# 20_FPGA_Power.net
KiCad netlist of a schematic drawn in Altium Designer
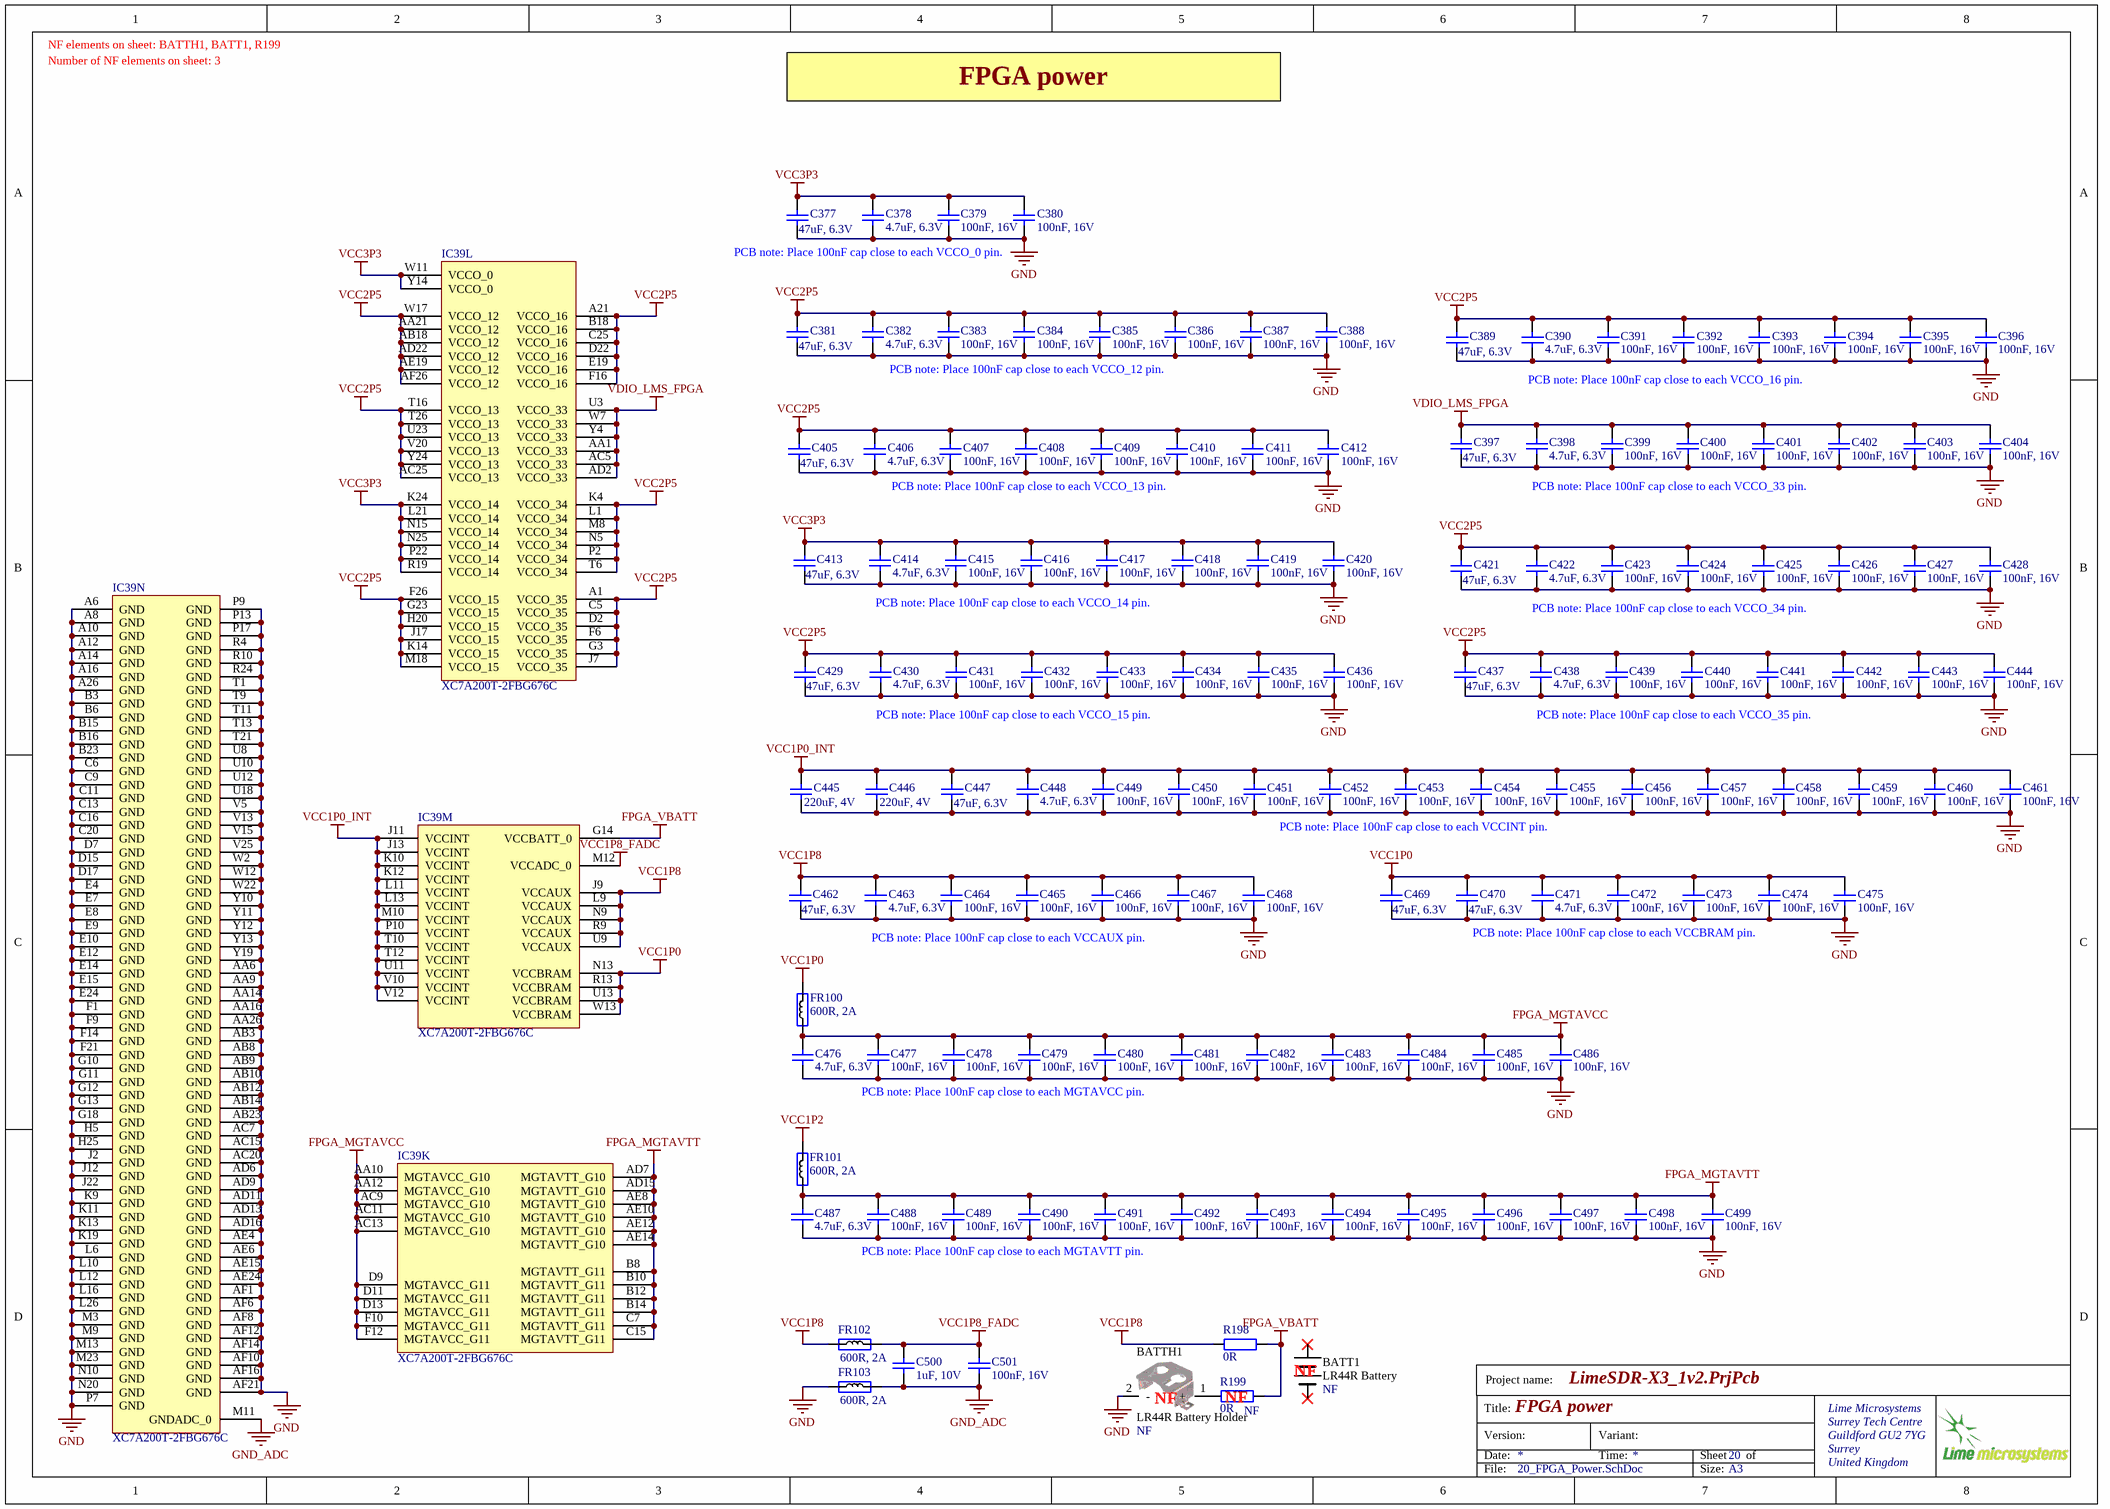
[diagram p0: 20_FPGA_Power.SchDoc]

(export (version "E")
  (design (tool "Eeschema 10.0.6"))
  (components
    (comp (ref "BATT1")
      (value "LR44R Battery")
      (fields (field (name "MANUFACTURER") "Murata") (field (name "ASSEMBLY INFO") "NF"))
      (libsource (lib "LimeMicroAltiumLib_schLib_r03") (part "LR44R_BATTERY"))
    )
    (comp (ref "BATTH1")
      (value "LR44R Battery Holder")
      (footprint "LR44R_BATTERY_HOLDER")
      (fields (field (name "MANUFACTURER") "Keystone Electronics") (field (name "ASSEMBLY INFO") "NF"))
      (libsource (lib "LimeMicroAltiumLib_schLib_r04") (part "LR44R_BATTERY_HOLDER"))
    )
    (comp (ref "C377")
      (value "47uF, 6.3V")
      (footprint "CAP1206")
      (fields
        (field (name "TOLERANCE") "±20%")
        (field (name "MANUFACTURER") "Samsung Electro-Mechanics")
        (field (name "MANUFACTURER PART NUMBER") "CL31A476MQHNNNE")
      )
      (libsource (lib "") (part "Cap_1206_2"))
    )
    (comp (ref "C378")
      (value "4.7uF, 6.3V")
      (footprint "CAP0402")
      (fields
        (field (name "MANUFACTURER") "Murata Electronics North America")
        (field (name "TOLERANCE") "±20%")
      )
      (libsource (lib "LimeMicroAltiumLib_schLib") (part "Cap_0402"))
    )
    (comp (ref "C379")
      (value "100nF, 16V")
      (footprint "CAP0402")
      (fields (field (name "MANUFACTURER") "Murata Electronics") (field (name "TOLERANCE") "10 %"))
      (libsource (lib "LimeMicroAltiumLib_schLib") (part "Cap_0402"))
    )
    (comp (ref "C380")
      (value "100nF, 16V")
      (footprint "CAP0402")
      (fields (field (name "MANUFACTURER") "Murata Electronics") (field (name "TOLERANCE") "10 %"))
      (libsource (lib "LimeMicroAltiumLib_schLib") (part "Cap_0402"))
    )
    (comp (ref "C381")
      (value "47uF, 6.3V")
      (footprint "CAP1206")
      (fields
        (field (name "TOLERANCE") "±20%")
        (field (name "MANUFACTURER") "Samsung Electro-Mechanics")
        (field (name "MANUFACTURER PART NUMBER") "CL31A476MQHNNNE")
      )
      (libsource (lib "") (part "Cap_1206_2"))
    )
    (comp (ref "C382")
      (value "4.7uF, 6.3V")
      (footprint "CAP0402")
      (fields
        (field (name "MANUFACTURER") "Murata Electronics North America")
        (field (name "TOLERANCE") "±20%")
      )
      (libsource (lib "LimeMicroAltiumLib_schLib") (part "Cap_0402"))
    )
    (comp (ref "C383")
      (value "100nF, 16V")
      (footprint "CAP0402")
      (fields (field (name "MANUFACTURER") "Murata Electronics") (field (name "TOLERANCE") "10 %"))
      (libsource (lib "LimeMicroAltiumLib_schLib") (part "Cap_0402"))
    )
    (comp (ref "C384")
      (value "100nF, 16V")
      (footprint "CAP0402")
      (fields (field (name "MANUFACTURER") "Murata Electronics") (field (name "TOLERANCE") "10 %"))
      (libsource (lib "LimeMicroAltiumLib_schLib") (part "Cap_0402"))
    )
    (comp (ref "C385")
      (value "100nF, 16V")
      (footprint "CAP0402")
      (fields (field (name "MANUFACTURER") "Murata Electronics") (field (name "TOLERANCE") "10 %"))
      (libsource (lib "") (part "Cap_0402_3"))
    )
    (comp (ref "C386")
      (value "100nF, 16V")
      (footprint "CAP0402")
      (fields (field (name "MANUFACTURER") "Murata Electronics") (field (name "TOLERANCE") "10 %"))
      (libsource (lib "") (part "Cap_0402_1"))
    )
    (comp (ref "C387")
      (value "100nF, 16V")
      (footprint "CAP0402")
      (fields (field (name "MANUFACTURER") "Murata Electronics") (field (name "TOLERANCE") "10 %"))
      (libsource (lib "") (part "Cap_0402_1"))
    )
    (comp (ref "C388")
      (value "100nF, 16V")
      (footprint "CAP0402")
      (fields (field (name "MANUFACTURER") "Murata Electronics") (field (name "TOLERANCE") "10 %"))
      (libsource (lib "LimeMicroAltiumLib_schLib") (part "Cap_0402"))
    )
    (comp (ref "C389")
      (value "47uF, 6.3V")
      (footprint "CAP1206")
      (fields
        (field (name "TOLERANCE") "±20%")
        (field (name "MANUFACTURER") "Samsung Electro-Mechanics")
        (field (name "MANUFACTURER PART NUMBER") "CL31A476MQHNNNE")
      )
      (libsource (lib "") (part "Cap_1206_2"))
    )
    (comp (ref "C390")
      (value "4.7uF, 6.3V")
      (footprint "CAP0402")
      (fields
        (field (name "MANUFACTURER") "Murata Electronics North America")
        (field (name "TOLERANCE") "±20%")
      )
      (libsource (lib "LimeMicroAltiumLib_schLib") (part "Cap_0402"))
    )
    (comp (ref "C391")
      (value "100nF, 16V")
      (footprint "CAP0402")
      (fields (field (name "MANUFACTURER") "Murata Electronics") (field (name "TOLERANCE") "10 %"))
      (libsource (lib "LimeMicroAltiumLib_schLib") (part "Cap_0402"))
    )
    (comp (ref "C392")
      (value "100nF, 16V")
      (footprint "CAP0402")
      (fields (field (name "MANUFACTURER") "Murata Electronics") (field (name "TOLERANCE") "10 %"))
      (libsource (lib "LimeMicroAltiumLib_schLib") (part "Cap_0402"))
    )
    (comp (ref "C393")
      (value "100nF, 16V")
      (footprint "CAP0402")
      (fields (field (name "MANUFACTURER") "Murata Electronics") (field (name "TOLERANCE") "10 %"))
      (libsource (lib "") (part "Cap_0402_3"))
    )
    (comp (ref "C394")
      (value "100nF, 16V")
      (footprint "CAP0402")
      (fields (field (name "MANUFACTURER") "Murata Electronics") (field (name "TOLERANCE") "10 %"))
      (libsource (lib "") (part "Cap_0402_1"))
    )
    (comp (ref "C395")
      (value "100nF, 16V")
      (footprint "CAP0402")
      (fields (field (name "MANUFACTURER") "Murata Electronics") (field (name "TOLERANCE") "10 %"))
      (libsource (lib "") (part "Cap_0402_1"))
    )
    (comp (ref "C396")
      (value "100nF, 16V")
      (footprint "CAP0402")
      (fields (field (name "MANUFACTURER") "Murata Electronics") (field (name "TOLERANCE") "10 %"))
      (libsource (lib "LimeMicroAltiumLib_schLib") (part "Cap_0402"))
    )
    (comp (ref "C397")
      (value "47uF, 6.3V")
      (footprint "CAP1206")
      (fields
        (field (name "TOLERANCE") "±20%")
        (field (name "MANUFACTURER") "Samsung Electro-Mechanics")
        (field (name "MANUFACTURER PART NUMBER") "CL31A476MQHNNNE")
      )
      (libsource (lib "LimeFPGAboard_schLib") (part "Cap_1206"))
    )
    (comp (ref "C398")
      (value "4.7uF, 6.3V")
      (footprint "CAP0402")
      (fields
        (field (name "MANUFACTURER") "Murata Electronics North America")
        (field (name "TOLERANCE") "±20%")
      )
      (libsource (lib "LimeMicroAltiumLib_schLib") (part "Cap_0402"))
    )
    (comp (ref "C399")
      (value "100nF, 16V")
      (footprint "CAP0402")
      (fields (field (name "MANUFACTURER") "Murata Electronics") (field (name "TOLERANCE") "10 %"))
      (libsource (lib "") (part "Cap_0402_1"))
    )
    (comp (ref "C400")
      (value "100nF, 16V")
      (footprint "CAP0402")
      (fields (field (name "MANUFACTURER") "Murata Electronics") (field (name "TOLERANCE") "10 %"))
      (libsource (lib "LimeMicroAltiumLib_schLib") (part "Cap_0402"))
    )
    (comp (ref "C401")
      (value "100nF, 16V")
      (footprint "CAP0402")
      (fields (field (name "MANUFACTURER") "Murata Electronics") (field (name "TOLERANCE") "10 %"))
      (libsource (lib "LimeMicroAltiumLib_schLib") (part "Cap_0402"))
    )
    (comp (ref "C402")
      (value "100nF, 16V")
      (footprint "CAP0402")
      (fields (field (name "MANUFACTURER") "Murata Electronics") (field (name "TOLERANCE") "10 %"))
      (libsource (lib "") (part "Cap_0402_3"))
    )
    (comp (ref "C403")
      (value "100nF, 16V")
      (footprint "CAP0402")
      (fields (field (name "MANUFACTURER") "Murata Electronics") (field (name "TOLERANCE") "10 %"))
      (libsource (lib "") (part "Cap_0402_1"))
    )
    (comp (ref "C404")
      (value "100nF, 16V")
      (footprint "CAP0402")
      (fields (field (name "MANUFACTURER") "Murata Electronics") (field (name "TOLERANCE") "10 %"))
      (libsource (lib "") (part "Cap_0402_1"))
    )
    (comp (ref "C405")
      (value "47uF, 6.3V")
      (footprint "CAP1206")
      (fields
        (field (name "TOLERANCE") "±20%")
        (field (name "MANUFACTURER") "Samsung Electro-Mechanics")
        (field (name "MANUFACTURER PART NUMBER") "CL31A476MQHNNNE")
      )
      (libsource (lib "") (part "Cap_1206_1"))
    )
    (comp (ref "C406")
      (value "4.7uF, 6.3V")
      (footprint "CAP0402")
      (fields
        (field (name "MANUFACTURER") "Murata Electronics North America")
        (field (name "TOLERANCE") "±20%")
      )
      (libsource (lib "") (part "Cap_0402_1"))
    )
    (comp (ref "C407")
      (value "100nF, 16V")
      (footprint "CAP0402")
      (fields (field (name "MANUFACTURER") "Murata Electronics") (field (name "TOLERANCE") "10 %"))
      (libsource (lib "") (part "Cap_0402_3"))
    )
    (comp (ref "C408")
      (value "100nF, 16V")
      (footprint "CAP0402")
      (fields (field (name "MANUFACTURER") "Murata Electronics") (field (name "TOLERANCE") "10 %"))
      (libsource (lib "") (part "Cap_0402_1"))
    )
    (comp (ref "C409")
      (value "100nF, 16V")
      (footprint "CAP0402")
      (fields (field (name "MANUFACTURER") "Murata Electronics") (field (name "TOLERANCE") "10 %"))
      (libsource (lib "") (part "Cap_0402_1"))
    )
    (comp (ref "C410")
      (value "100nF, 16V")
      (footprint "CAP0402")
      (fields (field (name "MANUFACTURER") "Murata Electronics") (field (name "TOLERANCE") "10 %"))
      (libsource (lib "LimeMicroAltiumLib_schLib") (part "Cap_0402"))
    )
    (comp (ref "C411")
      (value "100nF, 16V")
      (footprint "CAP0402")
      (fields (field (name "MANUFACTURER") "Murata Electronics") (field (name "TOLERANCE") "10 %"))
      (libsource (lib "LimeMicroAltiumLib_schLib") (part "Cap_0402"))
    )
    (comp (ref "C412")
      (value "100nF, 16V")
      (footprint "CAP0402")
      (fields (field (name "MANUFACTURER") "Murata Electronics") (field (name "TOLERANCE") "10 %"))
      (libsource (lib "") (part "Cap_0402_3"))
    )
    (comp (ref "C413")
      (value "47uF, 6.3V")
      (footprint "CAP1206")
      (fields
        (field (name "TOLERANCE") "±20%")
        (field (name "MANUFACTURER") "Samsung Electro-Mechanics")
        (field (name "MANUFACTURER PART NUMBER") "CL31A476MQHNNNE")
      )
      (libsource (lib "") (part "Cap_1206_1"))
    )
    (comp (ref "C414")
      (value "4.7uF, 6.3V")
      (footprint "CAP0402")
      (fields
        (field (name "MANUFACTURER") "Murata Electronics North America")
        (field (name "TOLERANCE") "±20%")
      )
      (libsource (lib "") (part "Cap_0402_1"))
    )
    (comp (ref "C415")
      (value "100nF, 16V")
      (footprint "CAP0402")
      (fields (field (name "MANUFACTURER") "Murata Electronics") (field (name "TOLERANCE") "10 %"))
      (libsource (lib "") (part "Cap_0402_3"))
    )
    (comp (ref "C416")
      (value "100nF, 16V")
      (footprint "CAP0402")
      (fields (field (name "MANUFACTURER") "Murata Electronics") (field (name "TOLERANCE") "10 %"))
      (libsource (lib "") (part "Cap_0402_1"))
    )
    (comp (ref "C417")
      (value "100nF, 16V")
      (footprint "CAP0402")
      (fields (field (name "MANUFACTURER") "Murata Electronics") (field (name "TOLERANCE") "10 %"))
      (libsource (lib "") (part "Cap_0402_1"))
    )
    (comp (ref "C418")
      (value "100nF, 16V")
      (footprint "CAP0402")
      (fields (field (name "MANUFACTURER") "Murata Electronics") (field (name "TOLERANCE") "10 %"))
      (libsource (lib "LimeMicroAltiumLib_schLib") (part "Cap_0402"))
    )
    (comp (ref "C419")
      (value "100nF, 16V")
      (footprint "CAP0402")
      (fields (field (name "MANUFACTURER") "Murata Electronics") (field (name "TOLERANCE") "10 %"))
      (libsource (lib "LimeMicroAltiumLib_schLib") (part "Cap_0402"))
    )
    (comp (ref "C420")
      (value "100nF, 16V")
      (footprint "CAP0402")
      (fields (field (name "MANUFACTURER") "Murata Electronics") (field (name "TOLERANCE") "10 %"))
      (libsource (lib "") (part "Cap_0402_3"))
    )
    (comp (ref "C421")
      (value "47uF, 6.3V")
      (footprint "CAP1206")
      (fields
        (field (name "TOLERANCE") "±20%")
        (field (name "MANUFACTURER") "Samsung Electro-Mechanics")
        (field (name "MANUFACTURER PART NUMBER") "CL31A476MQHNNNE")
      )
      (libsource (lib "LimeFPGAboard_schLib") (part "Cap_1206"))
    )
    (comp (ref "C422")
      (value "4.7uF, 6.3V")
      (footprint "CAP0402")
      (fields
        (field (name "MANUFACTURER") "Murata Electronics North America")
        (field (name "TOLERANCE") "±20%")
      )
      (libsource (lib "LimeMicroAltiumLib_schLib") (part "Cap_0402"))
    )
    (comp (ref "C423")
      (value "100nF, 16V")
      (footprint "CAP0402")
      (fields (field (name "MANUFACTURER") "Murata Electronics") (field (name "TOLERANCE") "10 %"))
      (libsource (lib "") (part "Cap_0402_1"))
    )
    (comp (ref "C424")
      (value "100nF, 16V")
      (footprint "CAP0402")
      (fields (field (name "MANUFACTURER") "Murata Electronics") (field (name "TOLERANCE") "10 %"))
      (libsource (lib "LimeMicroAltiumLib_schLib") (part "Cap_0402"))
    )
    (comp (ref "C425")
      (value "100nF, 16V")
      (footprint "CAP0402")
      (fields (field (name "MANUFACTURER") "Murata Electronics") (field (name "TOLERANCE") "10 %"))
      (libsource (lib "LimeMicroAltiumLib_schLib") (part "Cap_0402"))
    )
    (comp (ref "C426")
      (value "100nF, 16V")
      (footprint "CAP0402")
      (fields (field (name "MANUFACTURER") "Murata Electronics") (field (name "TOLERANCE") "10 %"))
      (libsource (lib "") (part "Cap_0402_3"))
    )
    (comp (ref "C427")
      (value "100nF, 16V")
      (footprint "CAP0402")
      (fields (field (name "MANUFACTURER") "Murata Electronics") (field (name "TOLERANCE") "10 %"))
      (libsource (lib "") (part "Cap_0402_1"))
    )
    (comp (ref "C428")
      (value "100nF, 16V")
      (footprint "CAP0402")
      (fields (field (name "MANUFACTURER") "Murata Electronics") (field (name "TOLERANCE") "10 %"))
      (libsource (lib "") (part "Cap_0402_1"))
    )
    (comp (ref "C429")
      (value "47uF, 6.3V")
      (footprint "CAP1206")
      (fields
        (field (name "TOLERANCE") "±20%")
        (field (name "MANUFACTURER") "Samsung Electro-Mechanics")
        (field (name "MANUFACTURER PART NUMBER") "CL31A476MQHNNNE")
      )
      (libsource (lib "") (part "Cap_1206_1"))
    )
    (comp (ref "C430")
      (value "4.7uF, 6.3V")
      (footprint "CAP0402")
      (fields
        (field (name "MANUFACTURER") "Murata Electronics North America")
        (field (name "TOLERANCE") "±20%")
      )
      (libsource (lib "") (part "Cap_0402_1"))
    )
    (comp (ref "C431")
      (value "100nF, 16V")
      (footprint "CAP0402")
      (fields (field (name "MANUFACTURER") "Murata Electronics") (field (name "TOLERANCE") "10 %"))
      (libsource (lib "") (part "Cap_0402_3"))
    )
    (comp (ref "C432")
      (value "100nF, 16V")
      (footprint "CAP0402")
      (fields (field (name "MANUFACTURER") "Murata Electronics") (field (name "TOLERANCE") "10 %"))
      (libsource (lib "") (part "Cap_0402_1"))
    )
    (comp (ref "C433")
      (value "100nF, 16V")
      (footprint "CAP0402")
      (fields (field (name "MANUFACTURER") "Murata Electronics") (field (name "TOLERANCE") "10 %"))
      (libsource (lib "") (part "Cap_0402_1"))
    )
    (comp (ref "C434")
      (value "100nF, 16V")
      (footprint "CAP0402")
      (fields (field (name "MANUFACTURER") "Murata Electronics") (field (name "TOLERANCE") "10 %"))
      (libsource (lib "LimeMicroAltiumLib_schLib") (part "Cap_0402"))
    )
    (comp (ref "C435")
      (value "100nF, 16V")
      (footprint "CAP0402")
      (fields (field (name "MANUFACTURER") "Murata Electronics") (field (name "TOLERANCE") "10 %"))
      (libsource (lib "LimeMicroAltiumLib_schLib") (part "Cap_0402"))
    )
    (comp (ref "C436")
      (value "100nF, 16V")
      (footprint "CAP0402")
      (fields (field (name "MANUFACTURER") "Murata Electronics") (field (name "TOLERANCE") "10 %"))
      (libsource (lib "") (part "Cap_0402_3"))
    )
    (comp (ref "C437")
      (value "47uF, 6.3V")
      (footprint "CAP1206")
      (fields
        (field (name "TOLERANCE") "±20%")
        (field (name "MANUFACTURER") "Samsung Electro-Mechanics")
        (field (name "MANUFACTURER PART NUMBER") "CL31A476MQHNNNE")
      )
      (libsource (lib "") (part "Cap_1206_1"))
    )
    (comp (ref "C438")
      (value "4.7uF, 6.3V")
      (footprint "CAP0402")
      (fields
        (field (name "MANUFACTURER") "Murata Electronics North America")
        (field (name "TOLERANCE") "±20%")
      )
      (libsource (lib "") (part "Cap_0402_3"))
    )
    (comp (ref "C439")
      (value "100nF, 16V")
      (footprint "CAP0402")
      (fields (field (name "MANUFACTURER") "Murata Electronics") (field (name "TOLERANCE") "10 %"))
      (libsource (lib "") (part "Cap_0402_1"))
    )
    (comp (ref "C440")
      (value "100nF, 16V")
      (footprint "CAP0402")
      (fields (field (name "MANUFACTURER") "Murata Electronics") (field (name "TOLERANCE") "10 %"))
      (libsource (lib "") (part "Cap_0402_1"))
    )
    (comp (ref "C441")
      (value "100nF, 16V")
      (footprint "CAP0402")
      (fields (field (name "MANUFACTURER") "Murata Electronics") (field (name "TOLERANCE") "10 %"))
      (libsource (lib "LimeMicroAltiumLib_schLib") (part "Cap_0402"))
    )
    (comp (ref "C442")
      (value "100nF, 16V")
      (footprint "CAP0402")
      (fields (field (name "MANUFACTURER") "Murata Electronics") (field (name "TOLERANCE") "10 %"))
      (libsource (lib "LimeMicroAltiumLib_schLib") (part "Cap_0402"))
    )
    (comp (ref "C443")
      (value "100nF, 16V")
      (footprint "CAP0402")
      (fields (field (name "MANUFACTURER") "Murata Electronics") (field (name "TOLERANCE") "10 %"))
      (libsource (lib "") (part "Cap_0402_3"))
    )
    (comp (ref "C444")
      (value "100nF, 16V")
      (footprint "CAP0402")
      (fields (field (name "MANUFACTURER") "Murata Electronics") (field (name "TOLERANCE") "10 %"))
      (libsource (lib "") (part "Cap_0402_1"))
    )
    (comp (ref "C445")
      (value "220uF, 4V")
      (footprint "CAP1206")
      (fields
        (field (name "MANUFACTURER") "Murata Electronics North America")
        (field (name "TOLERANCE") "±20%")
      )
      (libsource (lib "LimeFPGAboard_schLib") (part "Cap_1206"))
    )
    (comp (ref "C446")
      (value "220uF, 4V")
      (footprint "CAP1206")
      (fields
        (field (name "MANUFACTURER") "Murata Electronics North America")
        (field (name "TOLERANCE") "±20%")
      )
      (libsource (lib "") (part "Cap_1206_2"))
    )
    (comp (ref "C447")
      (value "47uF, 6.3V")
      (footprint "CAP1206")
      (fields
        (field (name "TOLERANCE") "±20%")
        (field (name "MANUFACTURER") "Samsung Electro-Mechanics")
        (field (name "MANUFACTURER PART NUMBER") "CL31A476MQHNNNE")
      )
      (libsource (lib "") (part "Cap_1206_2"))
    )
    (comp (ref "C448")
      (value "4.7uF, 6.3V")
      (footprint "CAP0402")
      (fields
        (field (name "MANUFACTURER") "Murata Electronics North America")
        (field (name "TOLERANCE") "±20%")
      )
      (libsource (lib "") (part "Cap_0402_1"))
    )
    (comp (ref "C449")
      (value "100nF, 16V")
      (footprint "CAP0402")
      (fields (field (name "MANUFACTURER") "Murata Electronics") (field (name "TOLERANCE") "10 %"))
      (libsource (lib "LimeMicroAltiumLib_schLib") (part "Cap_0402"))
    )
    (comp (ref "C450")
      (value "100nF, 16V")
      (footprint "CAP0402")
      (fields (field (name "MANUFACTURER") "Murata Electronics") (field (name "TOLERANCE") "10 %"))
      (libsource (lib "") (part "Cap_0402_3"))
    )
    (comp (ref "C451")
      (value "100nF, 16V")
      (footprint "CAP0402")
      (fields (field (name "MANUFACTURER") "Murata Electronics") (field (name "TOLERANCE") "10 %"))
      (libsource (lib "") (part "Cap_0402_1"))
    )
    (comp (ref "C452")
      (value "100nF, 16V")
      (footprint "CAP0402")
      (fields (field (name "MANUFACTURER") "Murata Electronics") (field (name "TOLERANCE") "10 %"))
      (libsource (lib "") (part "Cap_0402_1"))
    )
    (comp (ref "C453")
      (value "100nF, 16V")
      (footprint "CAP0402")
      (fields (field (name "MANUFACTURER") "Murata Electronics") (field (name "TOLERANCE") "10 %"))
      (libsource (lib "LimeMicroAltiumLib_schLib") (part "Cap_0402"))
    )
    (comp (ref "C454")
      (value "100nF, 16V")
      (footprint "CAP0402")
      (fields (field (name "MANUFACTURER") "Murata Electronics") (field (name "TOLERANCE") "10 %"))
      (libsource (lib "LimeMicroAltiumLib_schLib") (part "Cap_0402"))
    )
    (comp (ref "C455")
      (value "100nF, 16V")
      (footprint "CAP0402")
      (fields (field (name "MANUFACTURER") "Murata Electronics") (field (name "TOLERANCE") "10 %"))
      (libsource (lib "") (part "Cap_0402_3"))
    )
    (comp (ref "C456")
      (value "100nF, 16V")
      (footprint "CAP0402")
      (fields (field (name "MANUFACTURER") "Murata Electronics") (field (name "TOLERANCE") "10 %"))
      (libsource (lib "") (part "Cap_0402_1"))
    )
    (comp (ref "C457")
      (value "100nF, 16V")
      (footprint "CAP0402")
      (fields (field (name "MANUFACTURER") "Murata Electronics") (field (name "TOLERANCE") "10 %"))
      (libsource (lib "") (part "Cap_0402_1"))
    )
    (comp (ref "C458")
      (value "100nF, 16V")
      (footprint "CAP0402")
      (fields (field (name "MANUFACTURER") "Murata Electronics") (field (name "TOLERANCE") "10 %"))
      (libsource (lib "LimeMicroAltiumLib_schLib") (part "Cap_0402"))
    )
    (comp (ref "C459")
      (value "100nF, 16V")
      (footprint "CAP0402")
      (fields (field (name "MANUFACTURER") "Murata Electronics") (field (name "TOLERANCE") "10 %"))
      (libsource (lib "LimeMicroAltiumLib_schLib") (part "Cap_0402"))
    )
    (comp (ref "C460")
      (value "100nF, 16V")
      (footprint "CAP0402")
      (fields (field (name "MANUFACTURER") "Murata Electronics") (field (name "TOLERANCE") "10 %"))
      (libsource (lib "") (part "Cap_0402_3"))
    )
    (comp (ref "C461")
      (value "100nF, 16V")
      (footprint "CAP0402")
      (fields (field (name "MANUFACTURER") "Murata Electronics") (field (name "TOLERANCE") "10 %"))
      (libsource (lib "") (part "Cap_0402_1"))
    )
    (comp (ref "C462")
      (value "47uF, 6.3V")
      (footprint "CAP1206")
      (fields
        (field (name "TOLERANCE") "±20%")
        (field (name "MANUFACTURER") "Samsung Electro-Mechanics")
        (field (name "MANUFACTURER PART NUMBER") "CL31A476MQHNNNE")
      )
      (libsource (lib "") (part "Cap_1206_1"))
    )
    (comp (ref "C463")
      (value "4.7uF, 6.3V")
      (footprint "CAP0402")
      (fields
        (field (name "MANUFACTURER") "Murata Electronics North America")
        (field (name "TOLERANCE") "±20%")
      )
      (libsource (lib "") (part "Cap_0402_1"))
    )
    (comp (ref "C464")
      (value "100nF, 16V")
      (footprint "CAP0402")
      (fields (field (name "MANUFACTURER") "Murata Electronics") (field (name "TOLERANCE") "10 %"))
      (libsource (lib "") (part "Cap_0402_3"))
    )
    (comp (ref "C465")
      (value "100nF, 16V")
      (footprint "CAP0402")
      (fields (field (name "MANUFACTURER") "Murata Electronics") (field (name "TOLERANCE") "10 %"))
      (libsource (lib "") (part "Cap_0402_1"))
    )
    (comp (ref "C466")
      (value "100nF, 16V")
      (footprint "CAP0402")
      (fields (field (name "MANUFACTURER") "Murata Electronics") (field (name "TOLERANCE") "10 %"))
      (libsource (lib "") (part "Cap_0402_1"))
    )
    (comp (ref "C467")
      (value "100nF, 16V")
      (footprint "CAP0402")
      (fields (field (name "MANUFACTURER") "Murata Electronics") (field (name "TOLERANCE") "10 %"))
      (libsource (lib "LimeMicroAltiumLib_schLib") (part "Cap_0402"))
    )
    (comp (ref "C468")
      (value "100nF, 16V")
      (footprint "CAP0402")
      (fields (field (name "MANUFACTURER") "Murata Electronics") (field (name "TOLERANCE") "10 %"))
      (libsource (lib "LimeMicroAltiumLib_schLib") (part "Cap_0402"))
    )
    (comp (ref "C469")
      (value "47uF, 6.3V")
      (footprint "CAP1206")
      (fields
        (field (name "TOLERANCE") "±20%")
        (field (name "MANUFACTURER") "Samsung Electro-Mechanics")
        (field (name "MANUFACTURER PART NUMBER") "CL31A476MQHNNNE")
      )
      (libsource (lib "") (part "Cap_1206_1"))
    )
    (comp (ref "C470")
      (value "47uF, 6.3V")
      (footprint "CAP1206")
      (fields
        (field (name "TOLERANCE") "±20%")
        (field (name "MANUFACTURER") "Samsung Electro-Mechanics")
        (field (name "MANUFACTURER PART NUMBER") "CL31A476MQHNNNE")
      )
      (libsource (lib "LimeFPGAboard_schLib") (part "Cap_1206"))
    )
    (comp (ref "C471")
      (value "4.7uF, 6.3V")
      (footprint "CAP0402")
      (fields
        (field (name "MANUFACTURER") "Murata Electronics North America")
        (field (name "TOLERANCE") "±20%")
      )
      (libsource (lib "LimeMicroAltiumLib_schLib") (part "Cap_0402"))
    )
    (comp (ref "C472")
      (value "100nF, 16V")
      (footprint "CAP0402")
      (fields (field (name "MANUFACTURER") "Murata Electronics") (field (name "TOLERANCE") "10 %"))
      (libsource (lib "") (part "Cap_0402_1"))
    )
    (comp (ref "C473")
      (value "100nF, 16V")
      (footprint "CAP0402")
      (fields (field (name "MANUFACTURER") "Murata Electronics") (field (name "TOLERANCE") "10 %"))
      (libsource (lib "LimeMicroAltiumLib_schLib") (part "Cap_0402"))
    )
    (comp (ref "C474")
      (value "100nF, 16V")
      (footprint "CAP0402")
      (fields (field (name "MANUFACTURER") "Murata Electronics") (field (name "TOLERANCE") "10 %"))
      (libsource (lib "LimeMicroAltiumLib_schLib") (part "Cap_0402"))
    )
    (comp (ref "C475")
      (value "100nF, 16V")
      (footprint "CAP0402")
      (fields (field (name "MANUFACTURER") "Murata Electronics") (field (name "TOLERANCE") "10 %"))
      (libsource (lib "LimeMicroAltiumLib_schLib") (part "Cap_0402"))
    )
    (comp (ref "C476")
      (value "4.7uF, 6.3V")
      (footprint "CAP0402")
      (fields
        (field (name "MANUFACTURER") "Murata Electronics North America")
        (field (name "TOLERANCE") "±20%")
      )
      (libsource (lib "") (part "Cap_0402_3"))
    )
    (comp (ref "C477")
      (value "100nF, 16V")
      (footprint "CAP0402")
      (fields (field (name "MANUFACTURER") "Murata Electronics") (field (name "TOLERANCE") "10 %"))
      (libsource (lib "") (part "Cap_0402_1"))
    )
    (comp (ref "C478")
      (value "100nF, 16V")
      (footprint "CAP0402")
      (fields (field (name "MANUFACTURER") "Murata Electronics") (field (name "TOLERANCE") "10 %"))
      (libsource (lib "") (part "Cap_0402_1"))
    )
    (comp (ref "C479")
      (value "100nF, 16V")
      (footprint "CAP0402")
      (fields (field (name "MANUFACTURER") "Murata Electronics") (field (name "TOLERANCE") "10 %"))
      (libsource (lib "LimeMicroAltiumLib_schLib") (part "Cap_0402"))
    )
    (comp (ref "C480")
      (value "100nF, 16V")
      (footprint "CAP0402")
      (fields (field (name "MANUFACTURER") "Murata Electronics") (field (name "TOLERANCE") "10 %"))
      (libsource (lib "LimeMicroAltiumLib_schLib") (part "Cap_0402"))
    )
    (comp (ref "C481")
      (value "100nF, 16V")
      (footprint "CAP0402")
      (fields (field (name "MANUFACTURER") "Murata Electronics") (field (name "TOLERANCE") "10 %"))
      (libsource (lib "") (part "Cap_0402_2"))
    )
    (comp (ref "C482")
      (value "100nF, 16V")
      (footprint "CAP0402")
      (fields (field (name "MANUFACTURER") "Murata Electronics") (field (name "TOLERANCE") "10 %"))
      (libsource (lib "") (part "Cap_0402_1"))
    )
    (comp (ref "C483")
      (value "100nF, 16V")
      (footprint "CAP0402")
      (fields (field (name "MANUFACTURER") "Murata Electronics") (field (name "TOLERANCE") "10 %"))
      (libsource (lib "") (part "Cap_0402_1"))
    )
    (comp (ref "C484")
      (value "100nF, 16V")
      (footprint "CAP0402")
      (fields (field (name "MANUFACTURER") "Murata Electronics") (field (name "TOLERANCE") "10 %"))
      (libsource (lib "LimeMicroAltiumLib_schLib") (part "Cap_0402"))
    )
    (comp (ref "C485")
      (value "100nF, 16V")
      (footprint "CAP0402")
      (fields (field (name "MANUFACTURER") "Murata Electronics") (field (name "TOLERANCE") "10 %"))
      (libsource (lib "LimeMicroAltiumLib_schLib") (part "Cap_0402"))
    )
    (comp (ref "C486")
      (value "100nF, 16V")
      (footprint "CAP0402")
      (fields (field (name "MANUFACTURER") "Murata Electronics") (field (name "TOLERANCE") "10 %"))
      (libsource (lib "") (part "Cap_0402_2"))
    )
    (comp (ref "C487")
      (value "4.7uF, 6.3V")
      (footprint "CAP0402")
      (fields
        (field (name "MANUFACTURER") "Murata Electronics North America")
        (field (name "TOLERANCE") "±20%")
      )
      (libsource (lib "") (part "Cap_0402_1"))
    )
    (comp (ref "C488")
      (value "100nF, 16V")
      (footprint "CAP0402")
      (fields (field (name "MANUFACTURER") "Murata Electronics") (field (name "TOLERANCE") "10 %"))
      (libsource (lib "") (part "Cap_0402_1"))
    )
    (comp (ref "C489")
      (value "100nF, 16V")
      (footprint "CAP0402")
      (fields (field (name "MANUFACTURER") "Murata Electronics") (field (name "TOLERANCE") "10 %"))
      (libsource (lib "LimeMicroAltiumLib_schLib") (part "Cap_0402"))
    )
    (comp (ref "C490")
      (value "100nF, 16V")
      (footprint "CAP0402")
      (fields (field (name "MANUFACTURER") "Murata Electronics") (field (name "TOLERANCE") "10 %"))
      (libsource (lib "LimeMicroAltiumLib_schLib") (part "Cap_0402"))
    )
    (comp (ref "C491")
      (value "100nF, 16V")
      (footprint "CAP0402")
      (fields (field (name "MANUFACTURER") "Murata Electronics") (field (name "TOLERANCE") "10 %"))
      (libsource (lib "") (part "Cap_0402_3"))
    )
    (comp (ref "C492")
      (value "100nF, 16V")
      (footprint "CAP0402")
      (fields (field (name "MANUFACTURER") "Murata Electronics") (field (name "TOLERANCE") "10 %"))
      (libsource (lib "") (part "Cap_0402_1"))
    )
    (comp (ref "C493")
      (value "100nF, 16V")
      (footprint "CAP0402")
      (fields (field (name "MANUFACTURER") "Murata Electronics") (field (name "TOLERANCE") "10 %"))
      (libsource (lib "") (part "Cap_0402_1"))
    )
    (comp (ref "C494")
      (value "100nF, 16V")
      (footprint "CAP0402")
      (fields (field (name "MANUFACTURER") "Murata Electronics") (field (name "TOLERANCE") "10 %"))
      (libsource (lib "") (part "Cap_0402_1"))
    )
    (comp (ref "C495")
      (value "100nF, 16V")
      (footprint "CAP0402")
      (fields (field (name "MANUFACTURER") "Murata Electronics") (field (name "TOLERANCE") "10 %"))
      (libsource (lib "LimeMicroAltiumLib_schLib") (part "Cap_0402"))
    )
    (comp (ref "C496")
      (value "100nF, 16V")
      (footprint "CAP0402")
      (fields (field (name "MANUFACTURER") "Murata Electronics") (field (name "TOLERANCE") "10 %"))
      (libsource (lib "LimeMicroAltiumLib_schLib") (part "Cap_0402"))
    )
    (comp (ref "C497")
      (value "100nF, 16V")
      (footprint "CAP0402")
      (fields (field (name "MANUFACTURER") "Murata Electronics") (field (name "TOLERANCE") "10 %"))
      (libsource (lib "") (part "Cap_0402_2"))
    )
    (comp (ref "C498")
      (value "100nF, 16V")
      (footprint "CAP0402")
      (fields (field (name "MANUFACTURER") "Murata Electronics") (field (name "TOLERANCE") "10 %"))
      (libsource (lib "LimeMicroAltiumLib_schLib") (part "Cap_0402"))
    )
    (comp (ref "C499")
      (value "100nF, 16V")
      (footprint "CAP0402")
      (fields (field (name "MANUFACTURER") "Murata Electronics") (field (name "TOLERANCE") "10 %"))
      (libsource (lib "") (part "Cap_0402_2"))
    )
    (comp (ref "C500")
      (value "1uF, 10V")
      (footprint "CAP0402")
      (fields (field (name "MANUFACTURER") "TDK"))
      (libsource (lib "") (part "Cap_0402_3"))
    )
    (comp (ref "C501")
      (value "100nF, 16V")
      (footprint "CAP0402")
      (fields (field (name "MANUFACTURER") "Murata Electronics") (field (name "TOLERANCE") "10 %"))
      (libsource (lib "") (part "Cap_0402_1"))
    )
    (comp (ref "FR100")
      (value "600R, 2A")
      (footprint "RES0805")
      (fields (field (name "MANUFACTURER") "TDK Corporation"))
      (libsource (lib "LimeMicroAltiumLib_schLib") (part "Ferrite"))
    )
    (comp (ref "FR101")
      (value "600R, 2A")
      (footprint "RES0805")
      (fields (field (name "MANUFACTURER") "TDK Corporation"))
      (libsource (lib "LimeMicroAltiumLib_schLib") (part "Ferrite"))
    )
    (comp (ref "FR102")
      (value "600R, 2A")
      (footprint "RES0805")
      (fields (field (name "MANUFACTURER") "TDK Corporation"))
      (libsource (lib "LimeMicroAltiumLib_schLib") (part "Ferrite"))
    )
    (comp (ref "FR103")
      (value "600R, 2A")
      (footprint "RES0805")
      (fields (field (name "MANUFACTURER") "TDK Corporation"))
      (libsource (lib "LimeMicroAltiumLib_schLib") (part "Ferrite"))
    )
    (comp (ref "IC39")
      (value "XC7A200T-2FBG676C")
      (footprint "XC7A200T-2FBG676C_FBG676")
      (description "Artix-7 FPGA, 400 User I/Os, 8 GTP, 676-Ball BGA, Speed Grade 2, Commercial Grade, Pb-Free")
      (fields (field (name "MANUFACTURER") "Xilinx"))
      (libsource (lib "") (part "XC7A200T-2FBG676C_2"))
    )
    (comp (ref "R198")
      (value "0R")
      (footprint "RES0402")
      (fields (field (name "MANUFACTURER") "Yageo") (field (name "TOLERANCE") "Jumper"))
      (libsource (lib "LimeMicroAltiumLib_schLib") (part "Res_0402"))
    )
    (comp (ref "R199")
      (value "0R")
      (footprint "RES0402")
      (fields
        (field (name "ASSEMBLY INFO") "NF")
        (field (name "MANUFACTURER") "Yageo")
        (field (name "TOLERANCE") "Jumper")
      )
      (libsource (lib "LimeMicroAltiumLib_schLib") (part "Res_0402"))
    )
  )
  (nets
    (net (code "1") (name "FPGA_MGTAVCC") (class "Default")
      (node (ref "C476") (pin "2") (pinfunction "2_2") (pintype "passive"))
      (node (ref "C477") (pin "1") (pinfunction "1_1") (pintype "passive"))
      (node (ref "C478") (pin "1") (pinfunction "1_1") (pintype "passive"))
      (node (ref "C479") (pin "1") (pinfunction "1_1") (pintype "passive"))
      (node (ref "C480") (pin "1") (pinfunction "1_1") (pintype "passive"))
      (node (ref "C481") (pin "1") (pinfunction "1_1") (pintype "passive"))
      (node (ref "C482") (pin "1") (pinfunction "1_1") (pintype "passive"))
      (node (ref "C483") (pin "1") (pinfunction "1_1") (pintype "passive"))
      (node (ref "C484") (pin "1") (pinfunction "1_1") (pintype "passive"))
      (node (ref "C485") (pin "1") (pinfunction "1_1") (pintype "passive"))
      (node (ref "C486") (pin "1") (pinfunction "1_1") (pintype "passive"))
      (node (ref "FR100") (pin "1") (pinfunction "1_1") (pintype "passive"))
      (node (ref "IC39") (pin "AA10") (pinfunction "MGTAVCC_G10_AA10") (pintype "power_in"))
      (node (ref "IC39") (pin "AA12") (pinfunction "MGTAVCC_G10_AA12") (pintype "power_in"))
      (node (ref "IC39") (pin "AC11") (pinfunction "MGTAVCC_G10_AC11") (pintype "power_in"))
      (node (ref "IC39") (pin "AC13") (pinfunction "MGTAVCC_G10_AC13") (pintype "power_in"))
      (node (ref "IC39") (pin "AC9") (pinfunction "MGTAVCC_G10_AC9") (pintype "power_in"))
      (node (ref "IC39") (pin "D11") (pinfunction "MGTAVCC_G11_D11") (pintype "power_in"))
      (node (ref "IC39") (pin "D13") (pinfunction "MGTAVCC_G11_D13") (pintype "power_in"))
      (node (ref "IC39") (pin "D9") (pinfunction "MGTAVCC_G11_D9") (pintype "power_in"))
      (node (ref "IC39") (pin "F10") (pinfunction "MGTAVCC_G11_F10") (pintype "power_in"))
      (node (ref "IC39") (pin "F12") (pinfunction "MGTAVCC_G11_F12") (pintype "power_in"))
    )
    (net (code "2") (name "FPGA_MGTAVTT") (class "Default")
      (node (ref "C487") (pin "2") (pinfunction "2_2") (pintype "passive"))
      (node (ref "C488") (pin "1") (pinfunction "1_1") (pintype "passive"))
      (node (ref "C489") (pin "1") (pinfunction "1_1") (pintype "passive"))
      (node (ref "C490") (pin "1") (pinfunction "1_1") (pintype "passive"))
      (node (ref "C491") (pin "1") (pinfunction "1_1") (pintype "passive"))
      (node (ref "C492") (pin "1") (pinfunction "1_1") (pintype "passive"))
      (node (ref "C493") (pin "1") (pinfunction "1_1") (pintype "passive"))
      (node (ref "C494") (pin "1") (pinfunction "1_1") (pintype "passive"))
      (node (ref "C495") (pin "1") (pinfunction "1_1") (pintype "passive"))
      (node (ref "C496") (pin "1") (pinfunction "1_1") (pintype "passive"))
      (node (ref "C497") (pin "1") (pinfunction "1_1") (pintype "passive"))
      (node (ref "C498") (pin "1") (pinfunction "1_1") (pintype "passive"))
      (node (ref "C499") (pin "1") (pinfunction "1_1") (pintype "passive"))
      (node (ref "FR101") (pin "1") (pinfunction "1_1") (pintype "passive"))
      (node (ref "IC39") (pin "AD15") (pinfunction "MGTAVTT_G10_AD15") (pintype "power_in"))
      (node (ref "IC39") (pin "AD7") (pinfunction "MGTAVTT_G10_AD7") (pintype "power_in"))
      (node (ref "IC39") (pin "AE10") (pinfunction "MGTAVTT_G10_AE10") (pintype "power_in"))
      (node (ref "IC39") (pin "AE12") (pinfunction "MGTAVTT_G10_AE12") (pintype "power_in"))
      (node (ref "IC39") (pin "AE14") (pinfunction "MGTAVTT_G10_AE14") (pintype "power_in"))
      (node (ref "IC39") (pin "AE8") (pinfunction "MGTAVTT_G10_AE8") (pintype "power_in"))
      (node (ref "IC39") (pin "B10") (pinfunction "MGTAVTT_G11_B10") (pintype "power_in"))
      (node (ref "IC39") (pin "B12") (pinfunction "MGTAVTT_G11_B12") (pintype "power_in"))
      (node (ref "IC39") (pin "B14") (pinfunction "MGTAVTT_G11_B14") (pintype "power_in"))
      (node (ref "IC39") (pin "B8") (pinfunction "MGTAVTT_G11_B8") (pintype "power_in"))
      (node (ref "IC39") (pin "C15") (pinfunction "MGTAVTT_G11_C15") (pintype "power_in"))
      (node (ref "IC39") (pin "C7") (pinfunction "MGTAVTT_G11_C7") (pintype "power_in"))
    )
    (net (code "3") (name "FPGA_VBATT") (class "Default")
      (node (ref "IC39") (pin "G14") (pinfunction "VCCBATT_0_G14") (pintype "power_in"))
      (node (ref "R198") (pin "2") (pinfunction "2_2") (pintype "passive"))
      (node (ref "R199") (pin "2") (pinfunction "2_2") (pintype "passive"))
    )
    (net (code "4") (name "GND") (class "Default")
      (node (ref "BATTH1") (pin "2") (pinfunction "-_2") (pintype "passive"))
      (node (ref "C377") (pin "1") (pinfunction "1_1") (pintype "passive"))
      (node (ref "C378") (pin "1") (pinfunction "1_1") (pintype "passive"))
      (node (ref "C379") (pin "2") (pinfunction "2_2") (pintype "passive"))
      (node (ref "C380") (pin "2") (pinfunction "2_2") (pintype "passive"))
      (node (ref "C381") (pin "1") (pinfunction "1_1") (pintype "passive"))
      (node (ref "C382") (pin "1") (pinfunction "1_1") (pintype "passive"))
      (node (ref "C383") (pin "2") (pinfunction "2_2") (pintype "passive"))
      (node (ref "C384") (pin "2") (pinfunction "2_2") (pintype "passive"))
      (node (ref "C385") (pin "2") (pinfunction "2_2") (pintype "passive"))
      (node (ref "C386") (pin "2") (pinfunction "2_2") (pintype "passive"))
      (node (ref "C387") (pin "2") (pinfunction "2_2") (pintype "passive"))
      (node (ref "C388") (pin "2") (pinfunction "2_2") (pintype "passive"))
      (node (ref "C389") (pin "1") (pinfunction "1_1") (pintype "passive"))
      (node (ref "C390") (pin "1") (pinfunction "1_1") (pintype "passive"))
      (node (ref "C391") (pin "2") (pinfunction "2_2") (pintype "passive"))
      (node (ref "C392") (pin "2") (pinfunction "2_2") (pintype "passive"))
      (node (ref "C393") (pin "2") (pinfunction "2_2") (pintype "passive"))
      (node (ref "C394") (pin "2") (pinfunction "2_2") (pintype "passive"))
      (node (ref "C395") (pin "2") (pinfunction "2_2") (pintype "passive"))
      (node (ref "C396") (pin "2") (pinfunction "2_2") (pintype "passive"))
      (node (ref "C397") (pin "1") (pinfunction "1_1") (pintype "passive"))
      (node (ref "C398") (pin "1") (pinfunction "1_1") (pintype "passive"))
      (node (ref "C399") (pin "2") (pinfunction "2_2") (pintype "passive"))
      (node (ref "C400") (pin "2") (pinfunction "2_2") (pintype "passive"))
      (node (ref "C401") (pin "2") (pinfunction "2_2") (pintype "passive"))
      (node (ref "C402") (pin "2") (pinfunction "2_2") (pintype "passive"))
      (node (ref "C403") (pin "2") (pinfunction "2_2") (pintype "passive"))
      (node (ref "C404") (pin "2") (pinfunction "2_2") (pintype "passive"))
      (node (ref "C405") (pin "1") (pinfunction "1_1") (pintype "passive"))
      (node (ref "C406") (pin "1") (pinfunction "1_1") (pintype "passive"))
      (node (ref "C407") (pin "2") (pinfunction "2_2") (pintype "passive"))
      (node (ref "C408") (pin "2") (pinfunction "2_2") (pintype "passive"))
      (node (ref "C409") (pin "2") (pinfunction "2_2") (pintype "passive"))
      (node (ref "C410") (pin "2") (pinfunction "2_2") (pintype "passive"))
      (node (ref "C411") (pin "2") (pinfunction "2_2") (pintype "passive"))
      (node (ref "C412") (pin "2") (pinfunction "2_2") (pintype "passive"))
      (node (ref "C413") (pin "1") (pinfunction "1_1") (pintype "passive"))
      (node (ref "C414") (pin "1") (pinfunction "1_1") (pintype "passive"))
      (node (ref "C415") (pin "2") (pinfunction "2_2") (pintype "passive"))
      (node (ref "C416") (pin "2") (pinfunction "2_2") (pintype "passive"))
      (node (ref "C417") (pin "2") (pinfunction "2_2") (pintype "passive"))
      (node (ref "C418") (pin "2") (pinfunction "2_2") (pintype "passive"))
      (node (ref "C419") (pin "2") (pinfunction "2_2") (pintype "passive"))
      (node (ref "C420") (pin "2") (pinfunction "2_2") (pintype "passive"))
      (node (ref "C421") (pin "1") (pinfunction "1_1") (pintype "passive"))
      (node (ref "C422") (pin "1") (pinfunction "1_1") (pintype "passive"))
      (node (ref "C423") (pin "2") (pinfunction "2_2") (pintype "passive"))
      (node (ref "C424") (pin "2") (pinfunction "2_2") (pintype "passive"))
      (node (ref "C425") (pin "2") (pinfunction "2_2") (pintype "passive"))
      (node (ref "C426") (pin "2") (pinfunction "2_2") (pintype "passive"))
      (node (ref "C427") (pin "2") (pinfunction "2_2") (pintype "passive"))
      (node (ref "C428") (pin "2") (pinfunction "2_2") (pintype "passive"))
      (node (ref "C429") (pin "1") (pinfunction "1_1") (pintype "passive"))
      (node (ref "C430") (pin "1") (pinfunction "1_1") (pintype "passive"))
      (node (ref "C431") (pin "2") (pinfunction "2_2") (pintype "passive"))
      (node (ref "C432") (pin "2") (pinfunction "2_2") (pintype "passive"))
      (node (ref "C433") (pin "2") (pinfunction "2_2") (pintype "passive"))
      (node (ref "C434") (pin "2") (pinfunction "2_2") (pintype "passive"))
      (node (ref "C435") (pin "2") (pinfunction "2_2") (pintype "passive"))
      (node (ref "C436") (pin "2") (pinfunction "2_2") (pintype "passive"))
      (node (ref "C437") (pin "1") (pinfunction "1_1") (pintype "passive"))
      (node (ref "C438") (pin "1") (pinfunction "1_1") (pintype "passive"))
      (node (ref "C439") (pin "2") (pinfunction "2_2") (pintype "passive"))
      (node (ref "C440") (pin "2") (pinfunction "2_2") (pintype "passive"))
      (node (ref "C441") (pin "2") (pinfunction "2_2") (pintype "passive"))
      (node (ref "C442") (pin "2") (pinfunction "2_2") (pintype "passive"))
      (node (ref "C443") (pin "2") (pinfunction "2_2") (pintype "passive"))
      (node (ref "C444") (pin "2") (pinfunction "2_2") (pintype "passive"))
      (node (ref "C445") (pin "1") (pinfunction "1_1") (pintype "passive"))
      (node (ref "C446") (pin "1") (pinfunction "1_1") (pintype "passive"))
      (node (ref "C447") (pin "1") (pinfunction "1_1") (pintype "passive"))
      (node (ref "C448") (pin "1") (pinfunction "1_1") (pintype "passive"))
      (node (ref "C449") (pin "2") (pinfunction "2_2") (pintype "passive"))
      (node (ref "C450") (pin "2") (pinfunction "2_2") (pintype "passive"))
      (node (ref "C451") (pin "2") (pinfunction "2_2") (pintype "passive"))
      (node (ref "C452") (pin "2") (pinfunction "2_2") (pintype "passive"))
      (node (ref "C453") (pin "2") (pinfunction "2_2") (pintype "passive"))
      (node (ref "C454") (pin "2") (pinfunction "2_2") (pintype "passive"))
      (node (ref "C455") (pin "2") (pinfunction "2_2") (pintype "passive"))
      (node (ref "C456") (pin "2") (pinfunction "2_2") (pintype "passive"))
      (node (ref "C457") (pin "2") (pinfunction "2_2") (pintype "passive"))
      (node (ref "C458") (pin "2") (pinfunction "2_2") (pintype "passive"))
      (node (ref "C459") (pin "2") (pinfunction "2_2") (pintype "passive"))
      (node (ref "C460") (pin "2") (pinfunction "2_2") (pintype "passive"))
      (node (ref "C461") (pin "2") (pinfunction "2_2") (pintype "passive"))
      (node (ref "C462") (pin "1") (pinfunction "1_1") (pintype "passive"))
      (node (ref "C463") (pin "1") (pinfunction "1_1") (pintype "passive"))
      (node (ref "C464") (pin "2") (pinfunction "2_2") (pintype "passive"))
      (node (ref "C465") (pin "2") (pinfunction "2_2") (pintype "passive"))
      (node (ref "C466") (pin "2") (pinfunction "2_2") (pintype "passive"))
      (node (ref "C467") (pin "2") (pinfunction "2_2") (pintype "passive"))
      (node (ref "C468") (pin "2") (pinfunction "2_2") (pintype "passive"))
      (node (ref "C469") (pin "1") (pinfunction "1_1") (pintype "passive"))
      (node (ref "C470") (pin "1") (pinfunction "1_1") (pintype "passive"))
      (node (ref "C471") (pin "1") (pinfunction "1_1") (pintype "passive"))
      (node (ref "C472") (pin "2") (pinfunction "2_2") (pintype "passive"))
      (node (ref "C473") (pin "2") (pinfunction "2_2") (pintype "passive"))
      (node (ref "C474") (pin "2") (pinfunction "2_2") (pintype "passive"))
      (node (ref "C475") (pin "2") (pinfunction "2_2") (pintype "passive"))
      (node (ref "C476") (pin "1") (pinfunction "1_1") (pintype "passive"))
      (node (ref "C477") (pin "2") (pinfunction "2_2") (pintype "passive"))
      (node (ref "C478") (pin "2") (pinfunction "2_2") (pintype "passive"))
      (node (ref "C479") (pin "2") (pinfunction "2_2") (pintype "passive"))
      (node (ref "C480") (pin "2") (pinfunction "2_2") (pintype "passive"))
      (node (ref "C481") (pin "2") (pinfunction "2_2") (pintype "passive"))
      (node (ref "C482") (pin "2") (pinfunction "2_2") (pintype "passive"))
      (node (ref "C483") (pin "2") (pinfunction "2_2") (pintype "passive"))
      (node (ref "C484") (pin "2") (pinfunction "2_2") (pintype "passive"))
      (node (ref "C485") (pin "2") (pinfunction "2_2") (pintype "passive"))
      (node (ref "C486") (pin "2") (pinfunction "2_2") (pintype "passive"))
      (node (ref "C487") (pin "1") (pinfunction "1_1") (pintype "passive"))
      (node (ref "C488") (pin "2") (pinfunction "2_2") (pintype "passive"))
      (node (ref "C489") (pin "2") (pinfunction "2_2") (pintype "passive"))
      (node (ref "C490") (pin "2") (pinfunction "2_2") (pintype "passive"))
      (node (ref "C491") (pin "2") (pinfunction "2_2") (pintype "passive"))
      (node (ref "C492") (pin "2") (pinfunction "2_2") (pintype "passive"))
      (node (ref "C493") (pin "2") (pinfunction "2_2") (pintype "passive"))
      (node (ref "C494") (pin "2") (pinfunction "2_2") (pintype "passive"))
      (node (ref "C495") (pin "2") (pinfunction "2_2") (pintype "passive"))
      (node (ref "C496") (pin "2") (pinfunction "2_2") (pintype "passive"))
      (node (ref "C497") (pin "2") (pinfunction "2_2") (pintype "passive"))
      (node (ref "C498") (pin "2") (pinfunction "2_2") (pintype "passive"))
      (node (ref "C499") (pin "2") (pinfunction "2_2") (pintype "passive"))
      (node (ref "FR103") (pin "1") (pinfunction "1_1") (pintype "passive"))
      (node (ref "IC39") (pin "A10") (pinfunction "GND_A10") (pintype "power_in"))
      (node (ref "IC39") (pin "A12") (pinfunction "GND_A12") (pintype "power_in"))
      (node (ref "IC39") (pin "A14") (pinfunction "GND_A14") (pintype "power_in"))
      (node (ref "IC39") (pin "A16") (pinfunction "GND_A16") (pintype "power_in"))
      (node (ref "IC39") (pin "A26") (pinfunction "GND_A26") (pintype "power_in"))
      (node (ref "IC39") (pin "A6") (pinfunction "GND_A6") (pintype "power_in"))
      (node (ref "IC39") (pin "A8") (pinfunction "GND_A8") (pintype "power_in"))
      (node (ref "IC39") (pin "AA14") (pinfunction "GND_AA14") (pintype "power_in"))
      (node (ref "IC39") (pin "AA16") (pinfunction "GND_AA16") (pintype "power_in"))
      (node (ref "IC39") (pin "AA26") (pinfunction "GND_AA26") (pintype "power_in"))
      (node (ref "IC39") (pin "AA6") (pinfunction "GND_AA6") (pintype "power_in"))
      (node (ref "IC39") (pin "AA9") (pinfunction "GND_AA9") (pintype "power_in"))
      (node (ref "IC39") (pin "AB10") (pinfunction "GND_AB10") (pintype "power_in"))
      (node (ref "IC39") (pin "AB12") (pinfunction "GND_AB12") (pintype "power_in"))
      (node (ref "IC39") (pin "AB14") (pinfunction "GND_AB14") (pintype "power_in"))
      (node (ref "IC39") (pin "AB23") (pinfunction "GND_AB23") (pintype "power_in"))
      (node (ref "IC39") (pin "AB3") (pinfunction "GND_AB3") (pintype "power_in"))
      (node (ref "IC39") (pin "AB8") (pinfunction "GND_AB8") (pintype "power_in"))
      (node (ref "IC39") (pin "AB9") (pinfunction "GND_AB9") (pintype "power_in"))
      (node (ref "IC39") (pin "AC15") (pinfunction "GND_AC15") (pintype "power_in"))
      (node (ref "IC39") (pin "AC20") (pinfunction "GND_AC20") (pintype "power_in"))
      (node (ref "IC39") (pin "AC7") (pinfunction "GND_AC7") (pintype "power_in"))
      (node (ref "IC39") (pin "AD11") (pinfunction "GND_AD11") (pintype "power_in"))
      (node (ref "IC39") (pin "AD13") (pinfunction "GND_AD13") (pintype "power_in"))
      (node (ref "IC39") (pin "AD16") (pinfunction "GND_AD16") (pintype "power_in"))
      (node (ref "IC39") (pin "AD6") (pinfunction "GND_AD6") (pintype "power_in"))
      (node (ref "IC39") (pin "AD9") (pinfunction "GND_AD9") (pintype "power_in"))
      (node (ref "IC39") (pin "AE15") (pinfunction "GND_AE15") (pintype "power_in"))
      (node (ref "IC39") (pin "AE24") (pinfunction "GND_AE24") (pintype "power_in"))
      (node (ref "IC39") (pin "AE4") (pinfunction "GND_AE4") (pintype "power_in"))
      (node (ref "IC39") (pin "AE6") (pinfunction "GND_AE6") (pintype "power_in"))
      (node (ref "IC39") (pin "AF1") (pinfunction "GND_AF1") (pintype "power_in"))
      (node (ref "IC39") (pin "AF10") (pinfunction "GND_AF10") (pintype "power_in"))
      (node (ref "IC39") (pin "AF12") (pinfunction "GND_AF12") (pintype "power_in"))
      (node (ref "IC39") (pin "AF14") (pinfunction "GND_AF14") (pintype "power_in"))
      (node (ref "IC39") (pin "AF16") (pinfunction "GND_AF16") (pintype "power_in"))
      (node (ref "IC39") (pin "AF21") (pinfunction "GND_AF21") (pintype "power_in"))
      (node (ref "IC39") (pin "AF6") (pinfunction "GND_AF6") (pintype "power_in"))
      (node (ref "IC39") (pin "AF8") (pinfunction "GND_AF8") (pintype "power_in"))
      (node (ref "IC39") (pin "B15") (pinfunction "GND_B15") (pintype "power_in"))
      (node (ref "IC39") (pin "B16") (pinfunction "GND_B16") (pintype "power_in"))
      (node (ref "IC39") (pin "B23") (pinfunction "GND_B23") (pintype "power_in"))
      (node (ref "IC39") (pin "B3") (pinfunction "GND_B3") (pintype "power_in"))
      (node (ref "IC39") (pin "B6") (pinfunction "GND_B6") (pintype "power_in"))
      (node (ref "IC39") (pin "C11") (pinfunction "GND_C11") (pintype "power_in"))
      (node (ref "IC39") (pin "C13") (pinfunction "GND_C13") (pintype "power_in"))
      (node (ref "IC39") (pin "C16") (pinfunction "GND_C16") (pintype "power_in"))
      (node (ref "IC39") (pin "C20") (pinfunction "GND_C20") (pintype "power_in"))
      (node (ref "IC39") (pin "C6") (pinfunction "GND_C6") (pintype "power_in"))
      (node (ref "IC39") (pin "C9") (pinfunction "GND_C9") (pintype "power_in"))
      (node (ref "IC39") (pin "D15") (pinfunction "GND_D15") (pintype "power_in"))
      (node (ref "IC39") (pin "D17") (pinfunction "GND_D17") (pintype "power_in"))
      (node (ref "IC39") (pin "D7") (pinfunction "GND_D7") (pintype "power_in"))
      (node (ref "IC39") (pin "E10") (pinfunction "GND_E10") (pintype "power_in"))
      (node (ref "IC39") (pin "E12") (pinfunction "GND_E12") (pintype "power_in"))
      (node (ref "IC39") (pin "E14") (pinfunction "GND_E14") (pintype "power_in"))
      (node (ref "IC39") (pin "E15") (pinfunction "GND_E15") (pintype "power_in"))
      (node (ref "IC39") (pin "E24") (pinfunction "GND_E24") (pintype "power_in"))
      (node (ref "IC39") (pin "E4") (pinfunction "GND_E4") (pintype "power_in"))
      (node (ref "IC39") (pin "E7") (pinfunction "GND_E7") (pintype "power_in"))
      (node (ref "IC39") (pin "E8") (pinfunction "GND_E8") (pintype "power_in"))
      (node (ref "IC39") (pin "E9") (pinfunction "GND_E9") (pintype "power_in"))
      (node (ref "IC39") (pin "F1") (pinfunction "GND_F1") (pintype "power_in"))
      (node (ref "IC39") (pin "F14") (pinfunction "GND_F14") (pintype "power_in"))
      (node (ref "IC39") (pin "F21") (pinfunction "GND_F21") (pintype "power_in"))
      (node (ref "IC39") (pin "F9") (pinfunction "GND_F9") (pintype "power_in"))
      (node (ref "IC39") (pin "G10") (pinfunction "GND_G10") (pintype "power_in"))
      (node (ref "IC39") (pin "G11") (pinfunction "GND_G11") (pintype "power_in"))
      (node (ref "IC39") (pin "G12") (pinfunction "GND_G12") (pintype "power_in"))
      (node (ref "IC39") (pin "G13") (pinfunction "GND_G13") (pintype "power_in"))
      (node (ref "IC39") (pin "G18") (pinfunction "GND_G18") (pintype "power_in"))
      (node (ref "IC39") (pin "H25") (pinfunction "GND_H25") (pintype "power_in"))
      (node (ref "IC39") (pin "H5") (pinfunction "GND_H5") (pintype "power_in"))
      (node (ref "IC39") (pin "J12") (pinfunction "GND_J12") (pintype "power_in"))
      (node (ref "IC39") (pin "J2") (pinfunction "GND_J2") (pintype "power_in"))
      (node (ref "IC39") (pin "J22") (pinfunction "GND_J22") (pintype "power_in"))
      (node (ref "IC39") (pin "K11") (pinfunction "GND_K11") (pintype "power_in"))
      (node (ref "IC39") (pin "K13") (pinfunction "GND_K13") (pintype "power_in"))
      (node (ref "IC39") (pin "K19") (pinfunction "GND_K19") (pintype "power_in"))
      (node (ref "IC39") (pin "K9") (pinfunction "GND_K9") (pintype "power_in"))
      (node (ref "IC39") (pin "L10") (pinfunction "GND_L10") (pintype "power_in"))
      (node (ref "IC39") (pin "L12") (pinfunction "GND_L12") (pintype "power_in"))
      (node (ref "IC39") (pin "L16") (pinfunction "GND_L16") (pintype "power_in"))
      (node (ref "IC39") (pin "L26") (pinfunction "GND_L26") (pintype "power_in"))
      (node (ref "IC39") (pin "L6") (pinfunction "GND_L6") (pintype "power_in"))
      (node (ref "IC39") (pin "M13") (pinfunction "GND_M13") (pintype "power_in"))
      (node (ref "IC39") (pin "M23") (pinfunction "GND_M23") (pintype "power_in"))
      (node (ref "IC39") (pin "M3") (pinfunction "GND_M3") (pintype "power_in"))
      (node (ref "IC39") (pin "M9") (pinfunction "GND_M9") (pintype "power_in"))
      (node (ref "IC39") (pin "N10") (pinfunction "GND_N10") (pintype "power_in"))
      (node (ref "IC39") (pin "N20") (pinfunction "GND_N20") (pintype "power_in"))
      (node (ref "IC39") (pin "P13") (pinfunction "GND_P13") (pintype "power_in"))
      (node (ref "IC39") (pin "P17") (pinfunction "GND_P17") (pintype "power_in"))
      (node (ref "IC39") (pin "P7") (pinfunction "GND_P7") (pintype "power_in"))
      (node (ref "IC39") (pin "P9") (pinfunction "GND_P9") (pintype "power_in"))
      (node (ref "IC39") (pin "R10") (pinfunction "GND_R10") (pintype "power_in"))
      (node (ref "IC39") (pin "R24") (pinfunction "GND_R24") (pintype "power_in"))
      (node (ref "IC39") (pin "R4") (pinfunction "GND_R4") (pintype "power_in"))
      (node (ref "IC39") (pin "T1") (pinfunction "GND_T1") (pintype "power_in"))
      (node (ref "IC39") (pin "T11") (pinfunction "GND_T11") (pintype "power_in"))
      (node (ref "IC39") (pin "T13") (pinfunction "GND_T13") (pintype "power_in"))
      (node (ref "IC39") (pin "T21") (pinfunction "GND_T21") (pintype "power_in"))
      (node (ref "IC39") (pin "T9") (pinfunction "GND_T9") (pintype "power_in"))
      (node (ref "IC39") (pin "U10") (pinfunction "GND_U10") (pintype "power_in"))
      (node (ref "IC39") (pin "U12") (pinfunction "GND_U12") (pintype "power_in"))
      (node (ref "IC39") (pin "U18") (pinfunction "GND_U18") (pintype "power_in"))
      (node (ref "IC39") (pin "U8") (pinfunction "GND_U8") (pintype "power_in"))
      (node (ref "IC39") (pin "V13") (pinfunction "GND_V13") (pintype "power_in"))
      (node (ref "IC39") (pin "V15") (pinfunction "GND_V15") (pintype "power_in"))
      (node (ref "IC39") (pin "V25") (pinfunction "GND_V25") (pintype "power_in"))
      (node (ref "IC39") (pin "V5") (pinfunction "GND_V5") (pintype "power_in"))
      (node (ref "IC39") (pin "W12") (pinfunction "GND_W12") (pintype "power_in"))
      (node (ref "IC39") (pin "W2") (pinfunction "GND_W2") (pintype "power_in"))
      (node (ref "IC39") (pin "W22") (pinfunction "GND_W22") (pintype "power_in"))
      (node (ref "IC39") (pin "Y10") (pinfunction "GND_Y10") (pintype "power_in"))
      (node (ref "IC39") (pin "Y11") (pinfunction "GND_Y11") (pintype "power_in"))
      (node (ref "IC39") (pin "Y12") (pinfunction "GND_Y12") (pintype "power_in"))
      (node (ref "IC39") (pin "Y13") (pinfunction "GND_Y13") (pintype "power_in"))
      (node (ref "IC39") (pin "Y19") (pinfunction "GND_Y19") (pintype "power_in"))
    )
    (net (code "5") (name "GND_ADC") (class "Default")
      (node (ref "C500") (pin "1") (pinfunction "1_1") (pintype "passive"))
      (node (ref "C501") (pin "2") (pinfunction "2_2") (pintype "passive"))
      (node (ref "FR103") (pin "2") (pinfunction "2_2") (pintype "passive"))
      (node (ref "IC39") (pin "M11") (pinfunction "GNDADC_0_M11") (pintype "power_in"))
    )
    (net (code "6") (name "Net-(BATTH1-+)") (class "Default")
      (node (ref "BATTH1") (pin "1") (pinfunction "+_1") (pintype "passive"))
      (node (ref "R199") (pin "1") (pinfunction "1_1") (pintype "passive"))
    )
    (net (code "7") (name "VCC1P0") (class "Default")
      (node (ref "C469") (pin "2") (pinfunction "2_2") (pintype "passive"))
      (node (ref "C470") (pin "2") (pinfunction "2_2") (pintype "passive"))
      (node (ref "C471") (pin "2") (pinfunction "2_2") (pintype "passive"))
      (node (ref "C472") (pin "1") (pinfunction "1_1") (pintype "passive"))
      (node (ref "C473") (pin "1") (pinfunction "1_1") (pintype "passive"))
      (node (ref "C474") (pin "1") (pinfunction "1_1") (pintype "passive"))
      (node (ref "C475") (pin "1") (pinfunction "1_1") (pintype "passive"))
      (node (ref "FR100") (pin "2") (pinfunction "2_2") (pintype "passive"))
      (node (ref "IC39") (pin "N13") (pinfunction "VCCBRAM_N13") (pintype "power_in"))
      (node (ref "IC39") (pin "R13") (pinfunction "VCCBRAM_R13") (pintype "power_in"))
      (node (ref "IC39") (pin "U13") (pinfunction "VCCBRAM_U13") (pintype "power_in"))
      (node (ref "IC39") (pin "W13") (pinfunction "VCCBRAM_W13") (pintype "power_in"))
    )
    (net (code "8") (name "VCC1P0_INT") (class "Default")
      (node (ref "C445") (pin "2") (pinfunction "2_2") (pintype "passive"))
      (node (ref "C446") (pin "2") (pinfunction "2_2") (pintype "passive"))
      (node (ref "C447") (pin "2") (pinfunction "2_2") (pintype "passive"))
      (node (ref "C448") (pin "2") (pinfunction "2_2") (pintype "passive"))
      (node (ref "C449") (pin "1") (pinfunction "1_1") (pintype "passive"))
      (node (ref "C450") (pin "1") (pinfunction "1_1") (pintype "passive"))
      (node (ref "C451") (pin "1") (pinfunction "1_1") (pintype "passive"))
      (node (ref "C452") (pin "1") (pinfunction "1_1") (pintype "passive"))
      (node (ref "C453") (pin "1") (pinfunction "1_1") (pintype "passive"))
      (node (ref "C454") (pin "1") (pinfunction "1_1") (pintype "passive"))
      (node (ref "C455") (pin "1") (pinfunction "1_1") (pintype "passive"))
      (node (ref "C456") (pin "1") (pinfunction "1_1") (pintype "passive"))
      (node (ref "C457") (pin "1") (pinfunction "1_1") (pintype "passive"))
      (node (ref "C458") (pin "1") (pinfunction "1_1") (pintype "passive"))
      (node (ref "C459") (pin "1") (pinfunction "1_1") (pintype "passive"))
      (node (ref "C460") (pin "1") (pinfunction "1_1") (pintype "passive"))
      (node (ref "C461") (pin "1") (pinfunction "1_1") (pintype "passive"))
      (node (ref "IC39") (pin "J11") (pinfunction "VCCINT_J11") (pintype "power_in"))
      (node (ref "IC39") (pin "J13") (pinfunction "VCCINT_J13") (pintype "power_in"))
      (node (ref "IC39") (pin "K10") (pinfunction "VCCINT_K10") (pintype "power_in"))
      (node (ref "IC39") (pin "K12") (pinfunction "VCCINT_K12") (pintype "power_in"))
      (node (ref "IC39") (pin "L11") (pinfunction "VCCINT_L11") (pintype "power_in"))
      (node (ref "IC39") (pin "L13") (pinfunction "VCCINT_L13") (pintype "power_in"))
      (node (ref "IC39") (pin "M10") (pinfunction "VCCINT_M10") (pintype "power_in"))
      (node (ref "IC39") (pin "P10") (pinfunction "VCCINT_P10") (pintype "power_in"))
      (node (ref "IC39") (pin "T10") (pinfunction "VCCINT_T10") (pintype "power_in"))
      (node (ref "IC39") (pin "T12") (pinfunction "VCCINT_T12") (pintype "power_in"))
      (node (ref "IC39") (pin "U11") (pinfunction "VCCINT_U11") (pintype "power_in"))
      (node (ref "IC39") (pin "V10") (pinfunction "VCCINT_V10") (pintype "power_in"))
      (node (ref "IC39") (pin "V12") (pinfunction "VCCINT_V12") (pintype "power_in"))
    )
    (net (code "9") (name "VCC1P2") (class "Default")
      (node (ref "FR101") (pin "2") (pinfunction "2_2") (pintype "passive"))
    )
    (net (code "10") (name "VCC1P8") (class "Default")
      (node (ref "C462") (pin "2") (pinfunction "2_2") (pintype "passive"))
      (node (ref "C463") (pin "2") (pinfunction "2_2") (pintype "passive"))
      (node (ref "C464") (pin "1") (pinfunction "1_1") (pintype "passive"))
      (node (ref "C465") (pin "1") (pinfunction "1_1") (pintype "passive"))
      (node (ref "C466") (pin "1") (pinfunction "1_1") (pintype "passive"))
      (node (ref "C467") (pin "1") (pinfunction "1_1") (pintype "passive"))
      (node (ref "C468") (pin "1") (pinfunction "1_1") (pintype "passive"))
      (node (ref "FR102") (pin "1") (pinfunction "1_1") (pintype "passive"))
      (node (ref "IC39") (pin "J9") (pinfunction "VCCAUX_J9") (pintype "power_in"))
      (node (ref "IC39") (pin "L9") (pinfunction "VCCAUX_L9") (pintype "power_in"))
      (node (ref "IC39") (pin "N9") (pinfunction "VCCAUX_N9") (pintype "power_in"))
      (node (ref "IC39") (pin "R9") (pinfunction "VCCAUX_R9") (pintype "power_in"))
      (node (ref "IC39") (pin "U9") (pinfunction "VCCAUX_U9") (pintype "power_in"))
      (node (ref "R198") (pin "1") (pinfunction "1_1") (pintype "passive"))
    )
    (net (code "11") (name "VCC1P8_FADC") (class "Default")
      (node (ref "C500") (pin "2") (pinfunction "2_2") (pintype "passive"))
      (node (ref "C501") (pin "1") (pinfunction "1_1") (pintype "passive"))
      (node (ref "FR102") (pin "2") (pinfunction "2_2") (pintype "passive"))
      (node (ref "IC39") (pin "M12") (pinfunction "VCCADC_0_M12") (pintype "power_in"))
    )
    (net (code "12") (name "VCC2P5") (class "Default")
      (node (ref "C381") (pin "2") (pinfunction "2_2") (pintype "passive"))
      (node (ref "C382") (pin "2") (pinfunction "2_2") (pintype "passive"))
      (node (ref "C383") (pin "1") (pinfunction "1_1") (pintype "passive"))
      (node (ref "C384") (pin "1") (pinfunction "1_1") (pintype "passive"))
      (node (ref "C385") (pin "1") (pinfunction "1_1") (pintype "passive"))
      (node (ref "C386") (pin "1") (pinfunction "1_1") (pintype "passive"))
      (node (ref "C387") (pin "1") (pinfunction "1_1") (pintype "passive"))
      (node (ref "C388") (pin "1") (pinfunction "1_1") (pintype "passive"))
      (node (ref "C389") (pin "2") (pinfunction "2_2") (pintype "passive"))
      (node (ref "C390") (pin "2") (pinfunction "2_2") (pintype "passive"))
      (node (ref "C391") (pin "1") (pinfunction "1_1") (pintype "passive"))
      (node (ref "C392") (pin "1") (pinfunction "1_1") (pintype "passive"))
      (node (ref "C393") (pin "1") (pinfunction "1_1") (pintype "passive"))
      (node (ref "C394") (pin "1") (pinfunction "1_1") (pintype "passive"))
      (node (ref "C395") (pin "1") (pinfunction "1_1") (pintype "passive"))
      (node (ref "C396") (pin "1") (pinfunction "1_1") (pintype "passive"))
      (node (ref "C405") (pin "2") (pinfunction "2_2") (pintype "passive"))
      (node (ref "C406") (pin "2") (pinfunction "2_2") (pintype "passive"))
      (node (ref "C407") (pin "1") (pinfunction "1_1") (pintype "passive"))
      (node (ref "C408") (pin "1") (pinfunction "1_1") (pintype "passive"))
      (node (ref "C409") (pin "1") (pinfunction "1_1") (pintype "passive"))
      (node (ref "C410") (pin "1") (pinfunction "1_1") (pintype "passive"))
      (node (ref "C411") (pin "1") (pinfunction "1_1") (pintype "passive"))
      (node (ref "C412") (pin "1") (pinfunction "1_1") (pintype "passive"))
      (node (ref "C421") (pin "2") (pinfunction "2_2") (pintype "passive"))
      (node (ref "C422") (pin "2") (pinfunction "2_2") (pintype "passive"))
      (node (ref "C423") (pin "1") (pinfunction "1_1") (pintype "passive"))
      (node (ref "C424") (pin "1") (pinfunction "1_1") (pintype "passive"))
      (node (ref "C425") (pin "1") (pinfunction "1_1") (pintype "passive"))
      (node (ref "C426") (pin "1") (pinfunction "1_1") (pintype "passive"))
      (node (ref "C427") (pin "1") (pinfunction "1_1") (pintype "passive"))
      (node (ref "C428") (pin "1") (pinfunction "1_1") (pintype "passive"))
      (node (ref "C429") (pin "2") (pinfunction "2_2") (pintype "passive"))
      (node (ref "C430") (pin "2") (pinfunction "2_2") (pintype "passive"))
      (node (ref "C431") (pin "1") (pinfunction "1_1") (pintype "passive"))
      (node (ref "C432") (pin "1") (pinfunction "1_1") (pintype "passive"))
      (node (ref "C433") (pin "1") (pinfunction "1_1") (pintype "passive"))
      (node (ref "C434") (pin "1") (pinfunction "1_1") (pintype "passive"))
      (node (ref "C435") (pin "1") (pinfunction "1_1") (pintype "passive"))
      (node (ref "C436") (pin "1") (pinfunction "1_1") (pintype "passive"))
      (node (ref "C437") (pin "2") (pinfunction "2_2") (pintype "passive"))
      (node (ref "C438") (pin "2") (pinfunction "2_2") (pintype "passive"))
      (node (ref "C439") (pin "1") (pinfunction "1_1") (pintype "passive"))
      (node (ref "C440") (pin "1") (pinfunction "1_1") (pintype "passive"))
      (node (ref "C441") (pin "1") (pinfunction "1_1") (pintype "passive"))
      (node (ref "C442") (pin "1") (pinfunction "1_1") (pintype "passive"))
      (node (ref "C443") (pin "1") (pinfunction "1_1") (pintype "passive"))
      (node (ref "C444") (pin "1") (pinfunction "1_1") (pintype "passive"))
      (node (ref "IC39") (pin "A1") (pinfunction "VCCO_35_A1") (pintype "power_in"))
      (node (ref "IC39") (pin "A21") (pinfunction "VCCO_16_A21") (pintype "power_in"))
      (node (ref "IC39") (pin "AA21") (pinfunction "VCCO_12_AA21") (pintype "power_in"))
      (node (ref "IC39") (pin "AB18") (pinfunction "VCCO_12_AB18") (pintype "power_in"))
      (node (ref "IC39") (pin "AC25") (pinfunction "VCCO_13_AC25") (pintype "power_in"))
      (node (ref "IC39") (pin "AD22") (pinfunction "VCCO_12_AD22") (pintype "power_in"))
      (node (ref "IC39") (pin "AE19") (pinfunction "VCCO_12_AE19") (pintype "power_in"))
      (node (ref "IC39") (pin "AF26") (pinfunction "VCCO_12_AF26") (pintype "power_in"))
      (node (ref "IC39") (pin "B18") (pinfunction "VCCO_16_B18") (pintype "power_in"))
      (node (ref "IC39") (pin "C25") (pinfunction "VCCO_16_C25") (pintype "power_in"))
      (node (ref "IC39") (pin "C5") (pinfunction "VCCO_35_C5") (pintype "power_in"))
      (node (ref "IC39") (pin "D2") (pinfunction "VCCO_35_D2") (pintype "power_in"))
      (node (ref "IC39") (pin "D22") (pinfunction "VCCO_16_D22") (pintype "power_in"))
      (node (ref "IC39") (pin "E19") (pinfunction "VCCO_16_E19") (pintype "power_in"))
      (node (ref "IC39") (pin "F16") (pinfunction "VCCO_16_F16") (pintype "power_in"))
      (node (ref "IC39") (pin "F26") (pinfunction "VCCO_15_F26") (pintype "power_in"))
      (node (ref "IC39") (pin "F6") (pinfunction "VCCO_35_F6") (pintype "power_in"))
      (node (ref "IC39") (pin "G23") (pinfunction "VCCO_15_G23") (pintype "power_in"))
      (node (ref "IC39") (pin "G3") (pinfunction "VCCO_35_G3") (pintype "power_in"))
      (node (ref "IC39") (pin "H20") (pinfunction "VCCO_15_H20") (pintype "power_in"))
      (node (ref "IC39") (pin "J17") (pinfunction "VCCO_15_J17") (pintype "power_in"))
      (node (ref "IC39") (pin "J7") (pinfunction "VCCO_35_J7") (pintype "power_in"))
      (node (ref "IC39") (pin "K14") (pinfunction "VCCO_15_K14") (pintype "power_in"))
      (node (ref "IC39") (pin "K4") (pinfunction "VCCO_34_K4") (pintype "power_in"))
      (node (ref "IC39") (pin "L1") (pinfunction "VCCO_34_L1") (pintype "power_in"))
      (node (ref "IC39") (pin "M18") (pinfunction "VCCO_15_M18") (pintype "power_in"))
      (node (ref "IC39") (pin "M8") (pinfunction "VCCO_34_M8") (pintype "power_in"))
      (node (ref "IC39") (pin "N5") (pinfunction "VCCO_34_N5") (pintype "power_in"))
      (node (ref "IC39") (pin "P2") (pinfunction "VCCO_34_P2") (pintype "power_in"))
      (node (ref "IC39") (pin "T16") (pinfunction "VCCO_13_T16") (pintype "power_in"))
      (node (ref "IC39") (pin "T26") (pinfunction "VCCO_13_T26") (pintype "power_in"))
      (node (ref "IC39") (pin "T6") (pinfunction "VCCO_34_T6") (pintype "power_in"))
      (node (ref "IC39") (pin "U23") (pinfunction "VCCO_13_U23") (pintype "power_in"))
      (node (ref "IC39") (pin "V20") (pinfunction "VCCO_13_V20") (pintype "power_in"))
      (node (ref "IC39") (pin "W17") (pinfunction "VCCO_12_W17") (pintype "power_in"))
      (node (ref "IC39") (pin "Y24") (pinfunction "VCCO_13_Y24") (pintype "power_in"))
    )
    (net (code "13") (name "VCC3P3") (class "Default")
      (node (ref "C377") (pin "2") (pinfunction "2_2") (pintype "passive"))
      (node (ref "C378") (pin "2") (pinfunction "2_2") (pintype "passive"))
      (node (ref "C379") (pin "1") (pinfunction "1_1") (pintype "passive"))
      (node (ref "C380") (pin "1") (pinfunction "1_1") (pintype "passive"))
      (node (ref "C413") (pin "2") (pinfunction "2_2") (pintype "passive"))
      (node (ref "C414") (pin "2") (pinfunction "2_2") (pintype "passive"))
      (node (ref "C415") (pin "1") (pinfunction "1_1") (pintype "passive"))
      (node (ref "C416") (pin "1") (pinfunction "1_1") (pintype "passive"))
      (node (ref "C417") (pin "1") (pinfunction "1_1") (pintype "passive"))
      (node (ref "C418") (pin "1") (pinfunction "1_1") (pintype "passive"))
      (node (ref "C419") (pin "1") (pinfunction "1_1") (pintype "passive"))
      (node (ref "C420") (pin "1") (pinfunction "1_1") (pintype "passive"))
      (node (ref "IC39") (pin "K24") (pinfunction "VCCO_14_K24") (pintype "power_in"))
      (node (ref "IC39") (pin "L21") (pinfunction "VCCO_14_L21") (pintype "power_in"))
      (node (ref "IC39") (pin "N15") (pinfunction "VCCO_14_N15") (pintype "power_in"))
      (node (ref "IC39") (pin "N25") (pinfunction "VCCO_14_N25") (pintype "power_in"))
      (node (ref "IC39") (pin "P22") (pinfunction "VCCO_14_P22") (pintype "power_in"))
      (node (ref "IC39") (pin "R19") (pinfunction "VCCO_14_R19") (pintype "power_in"))
      (node (ref "IC39") (pin "W11") (pinfunction "VCCO_0_W11") (pintype "power_in"))
      (node (ref "IC39") (pin "Y14") (pinfunction "VCCO_0_Y14") (pintype "power_in"))
    )
    (net (code "14") (name "VDIO_LMS_FPGA") (class "Default")
      (node (ref "C397") (pin "2") (pinfunction "2_2") (pintype "passive"))
      (node (ref "C398") (pin "2") (pinfunction "2_2") (pintype "passive"))
      (node (ref "C399") (pin "1") (pinfunction "1_1") (pintype "passive"))
      (node (ref "C400") (pin "1") (pinfunction "1_1") (pintype "passive"))
      (node (ref "C401") (pin "1") (pinfunction "1_1") (pintype "passive"))
      (node (ref "C402") (pin "1") (pinfunction "1_1") (pintype "passive"))
      (node (ref "C403") (pin "1") (pinfunction "1_1") (pintype "passive"))
      (node (ref "C404") (pin "1") (pinfunction "1_1") (pintype "passive"))
      (node (ref "IC39") (pin "AA1") (pinfunction "VCCO_33_AA1") (pintype "power_in"))
      (node (ref "IC39") (pin "AC5") (pinfunction "VCCO_33_AC5") (pintype "power_in"))
      (node (ref "IC39") (pin "AD2") (pinfunction "VCCO_33_AD2") (pintype "power_in"))
      (node (ref "IC39") (pin "U3") (pinfunction "VCCO_33_U3") (pintype "power_in"))
      (node (ref "IC39") (pin "W7") (pinfunction "VCCO_33_W7") (pintype "power_in"))
      (node (ref "IC39") (pin "Y4") (pinfunction "VCCO_33_Y4") (pintype "power_in"))
    )
    (net (code "15") (name "unconnected-(BATT1-PadNEGATIVE)") (class "Default")
      (node (ref "BATT1") (pin "NEGATIVE") (pintype "passive+no_connect"))
    )
    (net (code "16") (name "unconnected-(BATT1-PadPOSITIVE)") (class "Default")
      (node (ref "BATT1") (pin "POSITIVE") (pintype "passive+no_connect"))
    )
  )
)
